# DogGone.net
KiCad netlist of a schematic drawn in EAGLE
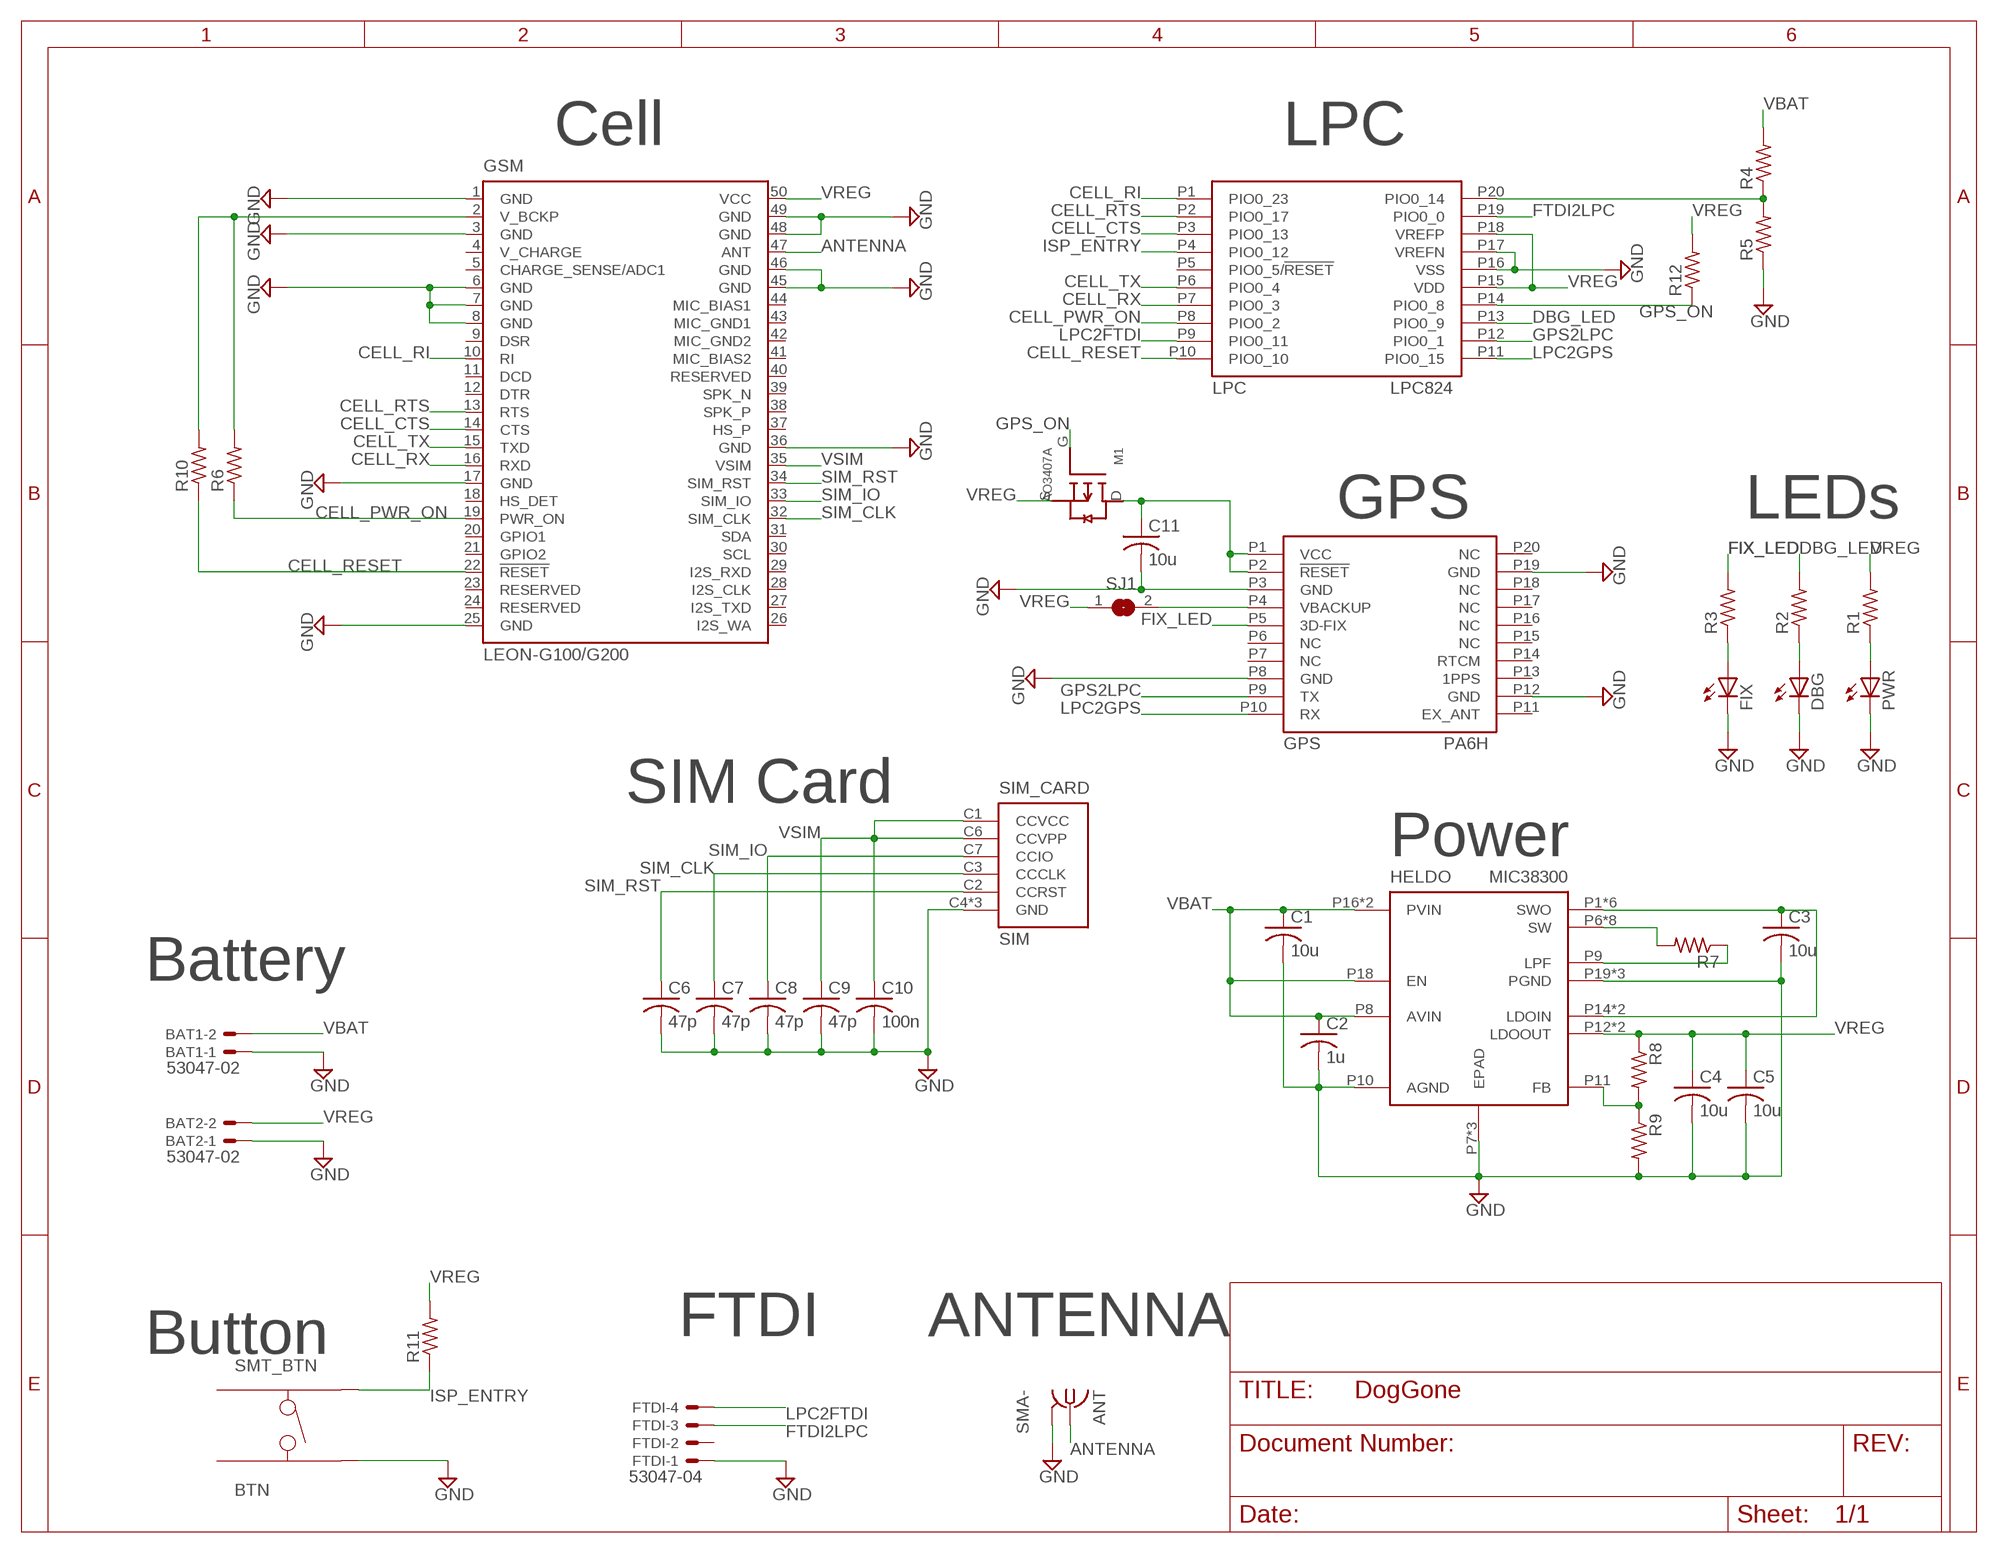
[diagram p0: schematic, sheet 1]

(export (version "E")
  (design (tool "Eeschema 10.0.6"))
  (components
    (comp (ref "ANT")
      (value "SMA-")
      (footprint "eagle-import:J502-ND-142-0701-801_806")
      (libsource (lib "eagle-import") (part "SMA-"))
    )
    (comp (ref "BAT1")
      (value "53047-02")
      (footprint "eagle-import:53047-02")
      (fields (field (name "MF") "MOLEX") (field (name "MPN") "53047-0210"))
      (libsource (lib "eagle-import") (part "53?-02047"))
    )
    (comp (ref "BAT2")
      (value "53047-02")
      (footprint "eagle-import:53047-02")
      (fields (field (name "MF") "MOLEX") (field (name "MPN") "53047-0210"))
      (libsource (lib "eagle-import") (part "53?-02047"))
    )
    (comp (ref "BTN")
      (value "SMT_BTN")
      (footprint "eagle-import:SMT_BUTTON")
      (libsource (lib "eagle-import") (part "SMT_BTN"))
    )
    (comp (ref "C1")
      (value "10u")
      (footprint "eagle-import:0603")
      (libsource (lib "eagle-import") (part "C0603"))
    )
    (comp (ref "C2")
      (value "1u")
      (footprint "eagle-import:0603")
      (libsource (lib "eagle-import") (part "C0603"))
    )
    (comp (ref "C3")
      (value "10u")
      (footprint "eagle-import:0603")
      (libsource (lib "eagle-import") (part "C0603"))
    )
    (comp (ref "C4")
      (value "10u")
      (footprint "eagle-import:0603")
      (libsource (lib "eagle-import") (part "C0603"))
    )
    (comp (ref "C5")
      (value "10u")
      (footprint "eagle-import:0603")
      (libsource (lib "eagle-import") (part "C0603"))
    )
    (comp (ref "C6")
      (value "47p")
      (footprint "eagle-import:0603")
      (libsource (lib "eagle-import") (part "C0603"))
    )
    (comp (ref "C7")
      (value "47p")
      (footprint "eagle-import:0603")
      (libsource (lib "eagle-import") (part "C0603"))
    )
    (comp (ref "C8")
      (value "47p")
      (footprint "eagle-import:0603")
      (libsource (lib "eagle-import") (part "C0603"))
    )
    (comp (ref "C9")
      (value "47p")
      (footprint "eagle-import:0603")
      (libsource (lib "eagle-import") (part "C0603"))
    )
    (comp (ref "C10")
      (value "100n")
      (footprint "eagle-import:0603")
      (libsource (lib "eagle-import") (part "C0603"))
    )
    (comp (ref "C11")
      (value "10u")
      (footprint "eagle-import:0603")
      (libsource (lib "eagle-import") (part "C0603"))
    )
    (comp (ref "DBG")
      (value "LEDCHIPLED_0603")
      (footprint "eagle-import:CHIPLED_0603")
      (libsource (lib "eagle-import") (part "LEDCHIPLED_0603"))
    )
    (comp (ref "FIX")
      (value "LEDCHIPLED_0603")
      (footprint "eagle-import:CHIPLED_0603")
      (libsource (lib "eagle-import") (part "LEDCHIPLED_0603"))
    )
    (comp (ref "FTDI")
      (value "53047-04")
      (footprint "eagle-import:53047-04")
      (fields (field (name "MF") "WALDOM/MOLEX") (field (name "MPN") "53047-0410"))
      (libsource (lib "eagle-import") (part "53?-04047"))
    )
    (comp (ref "GPS")
      (value "PA6H")
      (footprint "eagle-import:DFN20")
      (libsource (lib "eagle-import") (part "PA6H"))
    )
    (comp (ref "GSM")
      (value "LEON-G100/G200")
      (footprint "eagle-import:LEON-G100_G200")
      (libsource (lib "eagle-import") (part "LEON-G100/G200"))
    )
    (comp (ref "HELDO")
      (value "MIC38300")
      (footprint "eagle-import:MLF")
      (libsource (lib "eagle-import") (part "MIC38300_HELDO"))
    )
    (comp (ref "LPC")
      (value "LPC824")
      (footprint "eagle-import:TSSOP20")
      (libsource (lib "eagle-import") (part "LPC824M201JDH20"))
    )
    (comp (ref "M1")
      (value "AO3407A")
      (footprint "eagle-import:SOT23")
      (libsource (lib "eagle-import") (part "AO3407A"))
    )
    (comp (ref "PWR")
      (value "LEDCHIPLED_0603")
      (footprint "eagle-import:CHIPLED_0603")
      (libsource (lib "eagle-import") (part "LEDCHIPLED_0603"))
    )
    (comp (ref "R1")
      (value "R0603")
      (footprint "eagle-import:R0603")
      (libsource (lib "eagle-import") (part "R0603"))
    )
    (comp (ref "R2")
      (value "R0603")
      (footprint "eagle-import:R0603")
      (libsource (lib "eagle-import") (part "R0603"))
    )
    (comp (ref "R3")
      (value "R0603")
      (footprint "eagle-import:R0603")
      (libsource (lib "eagle-import") (part "R0603"))
    )
    (comp (ref "R4")
      (value "R0603")
      (footprint "eagle-import:R0603")
      (libsource (lib "eagle-import") (part "R0603"))
    )
    (comp (ref "R5")
      (value "R0603")
      (footprint "eagle-import:R0603")
      (libsource (lib "eagle-import") (part "R0603"))
    )
    (comp (ref "R6")
      (value "R0603")
      (footprint "eagle-import:R0603")
      (libsource (lib "eagle-import") (part "R0603"))
    )
    (comp (ref "R7")
      (value "R0603")
      (footprint "eagle-import:R0603")
      (libsource (lib "eagle-import") (part "R0603"))
    )
    (comp (ref "R8")
      (value "R0603")
      (footprint "eagle-import:R0603")
      (libsource (lib "eagle-import") (part "R0603"))
    )
    (comp (ref "R9")
      (value "R0603")
      (footprint "eagle-import:R0603")
      (libsource (lib "eagle-import") (part "R0603"))
    )
    (comp (ref "R10")
      (value "R0603")
      (footprint "eagle-import:R0603")
      (libsource (lib "eagle-import") (part "R0603"))
    )
    (comp (ref "R11")
      (value "R0603")
      (footprint "eagle-import:R0603")
      (libsource (lib "eagle-import") (part "R0603"))
    )
    (comp (ref "R12")
      (value "R0603")
      (footprint "eagle-import:R0603")
      (libsource (lib "eagle-import") (part "R0603"))
    )
    (comp (ref "SIM")
      (value "SIM_CARD")
      (footprint "eagle-import:SIM8050")
      (libsource (lib "eagle-import") (part "SIM_CARD"))
    )
    (comp (ref "SJ1") (value "SJ") (footprint "eagle-import:SJ") (libsource (lib "eagle-import") (part "SJ")))
  )
  (nets
    (net (code "1") (name "/ANTENNA") (class "Default")
      (node (ref "ANT") (pin "1") (pinfunction "1_1") (pintype "passive"))
      (node (ref "GSM") (pin "47") (pinfunction "ANT_47") (pintype "bidirectional"))
    )
    (net (code "2") (name "/CELL_CTS") (class "Default")
      (node (ref "GSM") (pin "14") (pinfunction "CTS_14") (pintype "input"))
      (node (ref "LPC") (pin "P3") (pinfunction "PIO0_13_P3") (pintype "bidirectional"))
    )
    (net (code "3") (name "/CELL_PWR_ON") (class "Default")
      (node (ref "GSM") (pin "19") (pinfunction "PWR_ON_19") (pintype "input"))
      (node (ref "LPC") (pin "P8") (pinfunction "PIO0_2_P8") (pintype "bidirectional"))
      (node (ref "R6") (pin "1") (pinfunction "1_1") (pintype "passive"))
    )
    (net (code "4") (name "/CELL_RESET") (class "Default")
      (node (ref "GSM") (pin "22") (pinfunction "~{RESET}_22") (pintype "input"))
      (node (ref "LPC") (pin "P10") (pinfunction "PIO0_10_P10") (pintype "bidirectional"))
      (node (ref "R10") (pin "1") (pinfunction "1_1") (pintype "passive"))
    )
    (net (code "5") (name "/CELL_RI") (class "Default")
      (node (ref "GSM") (pin "10") (pinfunction "RI_10") (pintype "input"))
      (node (ref "LPC") (pin "P1") (pinfunction "PIO0_23_P1") (pintype "bidirectional"))
    )
    (net (code "6") (name "/CELL_RTS") (class "Default")
      (node (ref "GSM") (pin "13") (pinfunction "RTS_13") (pintype "output"))
      (node (ref "LPC") (pin "P2") (pinfunction "PIO0_17_P2") (pintype "bidirectional"))
    )
    (net (code "7") (name "/CELL_RX") (class "Default")
      (node (ref "GSM") (pin "16") (pinfunction "RXD_16") (pintype "input"))
      (node (ref "LPC") (pin "P7") (pinfunction "PIO0_3_P7") (pintype "bidirectional"))
    )
    (net (code "8") (name "/CELL_TX") (class "Default")
      (node (ref "GSM") (pin "15") (pinfunction "TXD_15") (pintype "output"))
      (node (ref "LPC") (pin "P6") (pinfunction "PIO0_4_P6") (pintype "bidirectional"))
    )
    (net (code "9") (name "/DBG_LED") (class "Default")
      (node (ref "LPC") (pin "P13") (pinfunction "PIO0_9_P13") (pintype "bidirectional"))
      (node (ref "R2") (pin "2") (pinfunction "2_2") (pintype "passive"))
    )
    (net (code "10") (name "/FIX_LED") (class "Default")
      (node (ref "GPS") (pin "P5") (pinfunction "3D-FIX_P5") (pintype "bidirectional"))
      (node (ref "R3") (pin "2") (pinfunction "2_2") (pintype "passive"))
    )
    (net (code "11") (name "/FTDI2LPC") (class "Default")
      (node (ref "FTDI") (pin "3") (pinfunction "S_3") (pintype "passive"))
      (node (ref "LPC") (pin "P19") (pinfunction "PIO0_0_P19") (pintype "bidirectional"))
    )
    (net (code "12") (name "/GPS2LPC") (class "Default")
      (node (ref "GPS") (pin "P9") (pinfunction "TX_P9") (pintype "bidirectional"))
      (node (ref "LPC") (pin "P12") (pinfunction "PIO0_1_P12") (pintype "bidirectional"))
    )
    (net (code "13") (name "/GPS_ON") (class "Default")
      (node (ref "LPC") (pin "P14") (pinfunction "PIO0_8_P14") (pintype "bidirectional"))
      (node (ref "M1") (pin "G") (pinfunction "G_G") (pintype "bidirectional"))
      (node (ref "R12") (pin "1") (pinfunction "1_1") (pintype "passive"))
    )
    (net (code "14") (name "/ISP_ENTRY") (class "Default")
      (node (ref "BTN") (pin "P2") (pinfunction "P$2_P2") (pintype "bidirectional"))
      (node (ref "LPC") (pin "P4") (pinfunction "PIO0_12_P4") (pintype "bidirectional"))
      (node (ref "R11") (pin "1") (pinfunction "1_1") (pintype "passive"))
    )
    (net (code "15") (name "/LPC2FTDI") (class "Default")
      (node (ref "FTDI") (pin "4") (pinfunction "S_4") (pintype "passive"))
      (node (ref "LPC") (pin "P9") (pinfunction "PIO0_11_P9") (pintype "bidirectional"))
    )
    (net (code "16") (name "/LPC2GPS") (class "Default")
      (node (ref "GPS") (pin "P10") (pinfunction "RX_P10") (pintype "bidirectional"))
      (node (ref "LPC") (pin "P11") (pinfunction "PIO0_15_P11") (pintype "bidirectional"))
    )
    (net (code "17") (name "/SIM_CLK") (class "Default")
      (node (ref "C7") (pin "1") (pinfunction "1_1") (pintype "passive"))
      (node (ref "GSM") (pin "32") (pinfunction "SIM_CLK_32") (pintype "input"))
      (node (ref "SIM") (pin "C3") (pinfunction "CCCLK_C3") (pintype "bidirectional"))
    )
    (net (code "18") (name "/SIM_IO") (class "Default")
      (node (ref "C8") (pin "1") (pinfunction "1_1") (pintype "passive"))
      (node (ref "GSM") (pin "33") (pinfunction "SIM_IO_33") (pintype "input"))
      (node (ref "SIM") (pin "C7") (pinfunction "CCIO_C7") (pintype "bidirectional"))
    )
    (net (code "19") (name "/SIM_RST") (class "Default")
      (node (ref "C6") (pin "1") (pinfunction "1_1") (pintype "passive"))
      (node (ref "GSM") (pin "34") (pinfunction "SIM_RST_34") (pintype "input"))
      (node (ref "SIM") (pin "C2") (pinfunction "CCRST_C2") (pintype "bidirectional"))
    )
    (net (code "20") (name "/VBAT") (class "Default")
      (node (ref "BAT1") (pin "2") (pinfunction "S_2") (pintype "passive"))
      (node (ref "C1") (pin "1") (pinfunction "1_1") (pintype "passive"))
      (node (ref "C2") (pin "1") (pinfunction "1_1") (pintype "passive"))
      (node (ref "HELDO") (pin "P16") (pinfunction "PVIN_P16") (pintype "power_in"))
      (node (ref "HELDO") (pin "P17") (pinfunction "PVIN_P17") (pintype "power_in"))
      (node (ref "HELDO") (pin "P18") (pinfunction "EN_P18") (pintype "bidirectional"))
      (node (ref "HELDO") (pin "P8") (pinfunction "AVIN_P8") (pintype "power_in"))
      (node (ref "R4") (pin "2") (pinfunction "2_2") (pintype "passive"))
    )
    (net (code "21") (name "/VREG") (class "Default")
      (node (ref "BAT2") (pin "2") (pinfunction "S_2") (pintype "passive"))
      (node (ref "C4") (pin "1") (pinfunction "1_1") (pintype "passive"))
      (node (ref "C5") (pin "1") (pinfunction "1_1") (pintype "passive"))
      (node (ref "GSM") (pin "50") (pinfunction "VCC_50") (pintype "power_in"))
      (node (ref "HELDO") (pin "P12") (pinfunction "LDOOUT_P12") (pintype "power_in"))
      (node (ref "HELDO") (pin "P13") (pinfunction "LDOOUT_P13") (pintype "power_in"))
      (node (ref "LPC") (pin "P15") (pinfunction "VDD_P15") (pintype "power_in"))
      (node (ref "LPC") (pin "P18") (pinfunction "VREFP_P18") (pintype "bidirectional"))
      (node (ref "M1") (pin "S") (pinfunction "S_S") (pintype "bidirectional"))
      (node (ref "R1") (pin "2") (pinfunction "2_2") (pintype "passive"))
      (node (ref "R11") (pin "2") (pinfunction "2_2") (pintype "passive"))
      (node (ref "R12") (pin "2") (pinfunction "2_2") (pintype "passive"))
      (node (ref "R8") (pin "1") (pinfunction "1_1") (pintype "passive"))
      (node (ref "SJ1") (pin "1") (pinfunction "1_1") (pintype "passive"))
    )
    (net (code "22") (name "/VSIM") (class "Default")
      (node (ref "C10") (pin "1") (pinfunction "1_1") (pintype "passive"))
      (node (ref "C9") (pin "1") (pinfunction "1_1") (pintype "passive"))
      (node (ref "GSM") (pin "35") (pinfunction "VSIM_35") (pintype "input"))
      (node (ref "SIM") (pin "C1") (pinfunction "CCVCC_C1") (pintype "power_in"))
      (node (ref "SIM") (pin "C6") (pinfunction "CCVPP_C6") (pintype "power_in"))
    )
    (net (code "23") (name "GND") (class "Default")
      (node (ref "ANT") (pin "G@1") (pinfunction "GND_G@1") (pintype "passive"))
      (node (ref "ANT") (pin "G@2") (pinfunction "GND_G@2") (pintype "passive"))
      (node (ref "ANT") (pin "G@3") (pinfunction "GND_G@3") (pintype "passive"))
      (node (ref "ANT") (pin "G@4") (pinfunction "GND_G@4") (pintype "passive"))
      (node (ref "BAT1") (pin "1") (pinfunction "S_1") (pintype "passive"))
      (node (ref "BAT2") (pin "1") (pinfunction "S_1") (pintype "passive"))
      (node (ref "BTN") (pin "P4") (pinfunction "P$4_P4") (pintype "bidirectional"))
      (node (ref "C1") (pin "2") (pinfunction "2_2") (pintype "passive"))
      (node (ref "C10") (pin "2") (pinfunction "2_2") (pintype "passive"))
      (node (ref "C11") (pin "2") (pinfunction "2_2") (pintype "passive"))
      (node (ref "C2") (pin "2") (pinfunction "2_2") (pintype "passive"))
      (node (ref "C3") (pin "2") (pinfunction "2_2") (pintype "passive"))
      (node (ref "C4") (pin "2") (pinfunction "2_2") (pintype "passive"))
      (node (ref "C5") (pin "2") (pinfunction "2_2") (pintype "passive"))
      (node (ref "C6") (pin "2") (pinfunction "2_2") (pintype "passive"))
      (node (ref "C7") (pin "2") (pinfunction "2_2") (pintype "passive"))
      (node (ref "C8") (pin "2") (pinfunction "2_2") (pintype "passive"))
      (node (ref "C9") (pin "2") (pinfunction "2_2") (pintype "passive"))
      (node (ref "DBG") (pin "C") (pinfunction "C_C") (pintype "passive"))
      (node (ref "FIX") (pin "C") (pinfunction "C_C") (pintype "passive"))
      (node (ref "FTDI") (pin "1") (pinfunction "S_1") (pintype "passive"))
      (node (ref "GPS") (pin "P12") (pinfunction "GND_P12") (pintype "power_in"))
      (node (ref "GPS") (pin "P19") (pinfunction "GND_P19") (pintype "power_in"))
      (node (ref "GPS") (pin "P3") (pinfunction "GND_P3") (pintype "power_in"))
      (node (ref "GPS") (pin "P8") (pinfunction "GND_P8") (pintype "power_in"))
      (node (ref "GSM") (pin "1") (pinfunction "GND_1") (pintype "power_in"))
      (node (ref "GSM") (pin "17") (pinfunction "GND_17") (pintype "power_in"))
      (node (ref "GSM") (pin "25") (pinfunction "GND_25") (pintype "power_in"))
      (node (ref "GSM") (pin "3") (pinfunction "GND_3") (pintype "power_in"))
      (node (ref "GSM") (pin "36") (pinfunction "GND_36") (pintype "power_in"))
      (node (ref "GSM") (pin "45") (pinfunction "GND_45") (pintype "power_in"))
      (node (ref "GSM") (pin "46") (pinfunction "GND_46") (pintype "power_in"))
      (node (ref "GSM") (pin "48") (pinfunction "GND_48") (pintype "power_in"))
      (node (ref "GSM") (pin "49") (pinfunction "GND_49") (pintype "power_in"))
      (node (ref "GSM") (pin "6") (pinfunction "GND_6") (pintype "power_in"))
      (node (ref "GSM") (pin "7") (pinfunction "GND_7") (pintype "power_in"))
      (node (ref "GSM") (pin "8") (pinfunction "GND_8") (pintype "power_in"))
      (node (ref "HELDO") (pin "P10") (pinfunction "AGND_P10") (pintype "bidirectional"))
      (node (ref "HELDO") (pin "P19") (pinfunction "PGND_P19") (pintype "power_in"))
      (node (ref "HELDO") (pin "P20") (pinfunction "PGND_P20") (pintype "power_in"))
      (node (ref "HELDO") (pin "P21") (pinfunction "PGND_P21") (pintype "power_in"))
      (node (ref "HELDO") (pin "P22") (pinfunction "EPAD_P22") (pintype "power_in"))
      (node (ref "HELDO") (pin "P7") (pinfunction "EPAD_P7") (pintype "power_in"))
      (node (ref "HELDO") (pin "P8-21") (pinfunction "EPAD_P8-21") (pintype "power_in"))
      (node (ref "LPC") (pin "P16") (pinfunction "VSS_P16") (pintype "power_in"))
      (node (ref "LPC") (pin "P17") (pinfunction "VREFN_P17") (pintype "bidirectional"))
      (node (ref "PWR") (pin "C") (pinfunction "C_C") (pintype "passive"))
      (node (ref "R5") (pin "1") (pinfunction "1_1") (pintype "passive"))
      (node (ref "R9") (pin "2") (pinfunction "2_2") (pintype "passive"))
      (node (ref "SIM") (pin "C4") (pinfunction "GND_C4") (pintype "power_in"))
      (node (ref "SIM") (pin "C5") (pinfunction "GND_C5") (pintype "power_in"))
      (node (ref "SIM") (pin "C8") (pinfunction "GND_C8") (pintype "power_in"))
    )
    (net (code "24") (name "Net-(C3-Pad1)") (class "Default")
      (node (ref "C3") (pin "1") (pinfunction "1_1") (pintype "passive"))
      (node (ref "HELDO") (pin "P1") (pinfunction "SWO_P1") (pintype "passive"))
      (node (ref "HELDO") (pin "P1-5") (pinfunction "SWO_P1-5") (pintype "passive"))
      (node (ref "HELDO") (pin "P14") (pinfunction "LDOIN_P14") (pintype "power_in"))
      (node (ref "HELDO") (pin "P15") (pinfunction "LDOIN_P15") (pintype "power_in"))
      (node (ref "HELDO") (pin "P2") (pinfunction "SWO_P2") (pintype "passive"))
      (node (ref "HELDO") (pin "P3") (pinfunction "SWO_P3") (pintype "passive"))
      (node (ref "HELDO") (pin "P4") (pinfunction "SWO_P4") (pintype "passive"))
      (node (ref "HELDO") (pin "P5") (pinfunction "SWO_P5") (pintype "passive"))
    )
    (net (code "25") (name "Net-(DBG-PadA)") (class "Default")
      (node (ref "DBG") (pin "A") (pinfunction "A_A") (pintype "passive"))
      (node (ref "R2") (pin "1") (pinfunction "1_1") (pintype "passive"))
    )
    (net (code "26") (name "Net-(FIX-PadA)") (class "Default")
      (node (ref "FIX") (pin "A") (pinfunction "A_A") (pintype "passive"))
      (node (ref "R3") (pin "1") (pinfunction "1_1") (pintype "passive"))
    )
    (net (code "27") (name "Net-(GPS-VBACKUP)") (class "Default")
      (node (ref "GPS") (pin "P4") (pinfunction "VBACKUP_P4") (pintype "power_in"))
      (node (ref "SJ1") (pin "2") (pinfunction "2_2") (pintype "passive"))
    )
    (net (code "28") (name "Net-(GPS-VCC)") (class "Default")
      (node (ref "C11") (pin "1") (pinfunction "1_1") (pintype "passive"))
      (node (ref "GPS") (pin "P1") (pinfunction "VCC_P1") (pintype "power_in"))
      (node (ref "GPS") (pin "P2") (pinfunction "~{RESET}_P2") (pintype "bidirectional"))
      (node (ref "M1") (pin "D") (pinfunction "D_D") (pintype "bidirectional"))
    )
    (net (code "29") (name "Net-(GSM-V_BCKP)") (class "Default")
      (node (ref "GSM") (pin "2") (pinfunction "V_BCKP_2") (pintype "input"))
      (node (ref "R10") (pin "2") (pinfunction "2_2") (pintype "passive"))
      (node (ref "R6") (pin "2") (pinfunction "2_2") (pintype "passive"))
    )
    (net (code "30") (name "Net-(HELDO-FB)") (class "Default")
      (node (ref "HELDO") (pin "P11") (pinfunction "FB_P11") (pintype "bidirectional"))
      (node (ref "R8") (pin "2") (pinfunction "2_2") (pintype "passive"))
      (node (ref "R9") (pin "1") (pinfunction "1_1") (pintype "passive"))
    )
    (net (code "31") (name "Net-(HELDO-LPF)") (class "Default")
      (node (ref "HELDO") (pin "P9") (pinfunction "LPF_P9") (pintype "bidirectional"))
      (node (ref "R7") (pin "1") (pinfunction "1_1") (pintype "passive"))
    )
    (net (code "32") (name "Net-(HELDO-SW-PadP23)") (class "Default")
      (node (ref "HELDO") (pin "P23") (pinfunction "SW_P23") (pintype "bidirectional"))
      (node (ref "HELDO") (pin "P23-28") (pinfunction "SW_P23-28") (pintype "bidirectional"))
      (node (ref "HELDO") (pin "P24") (pinfunction "SW_P24") (pintype "bidirectional"))
      (node (ref "HELDO") (pin "P25") (pinfunction "SW_P25") (pintype "bidirectional"))
      (node (ref "HELDO") (pin "P26") (pinfunction "SW_P26") (pintype "bidirectional"))
      (node (ref "HELDO") (pin "P27") (pinfunction "SW_P27") (pintype "bidirectional"))
      (node (ref "HELDO") (pin "P28") (pinfunction "SW_P28") (pintype "bidirectional"))
      (node (ref "HELDO") (pin "P6") (pinfunction "SW_P6") (pintype "bidirectional"))
      (node (ref "R7") (pin "2") (pinfunction "2_2") (pintype "passive"))
    )
    (net (code "33") (name "Net-(LPC-PIO0_14)") (class "Default")
      (node (ref "LPC") (pin "P20") (pinfunction "PIO0_14_P20") (pintype "bidirectional"))
      (node (ref "R4") (pin "1") (pinfunction "1_1") (pintype "passive"))
      (node (ref "R5") (pin "2") (pinfunction "2_2") (pintype "passive"))
    )
    (net (code "34") (name "Net-(PWR-PadA)") (class "Default")
      (node (ref "PWR") (pin "A") (pinfunction "A_A") (pintype "passive"))
      (node (ref "R1") (pin "1") (pinfunction "1_1") (pintype "passive"))
    )
    (net (code "35") (name "unconnected-(BTN-P$1-PadP1)") (class "Default")
      (node (ref "BTN") (pin "P1") (pinfunction "P$1_P1") (pintype "bidirectional"))
    )
    (net (code "36") (name "unconnected-(BTN-P$3-PadP3)") (class "Default")
      (node (ref "BTN") (pin "P3") (pinfunction "P$3_P3") (pintype "bidirectional"))
    )
    (net (code "37") (name "unconnected-(FTDIB-S-Pad2)") (class "Default")
      (node (ref "FTDI") (pin "2") (pinfunction "S_2") (pintype "passive"))
    )
    (net (code "38") (name "unconnected-(GPS-1PPS-PadP13)") (class "Default")
      (node (ref "GPS") (pin "P13") (pinfunction "1PPS_P13") (pintype "bidirectional"))
    )
    (net (code "39") (name "unconnected-(GPS-EX_ANT-PadP11)") (class "Default")
      (node (ref "GPS") (pin "P11") (pinfunction "EX_ANT_P11") (pintype "passive"))
    )
    (net (code "40") (name "unconnected-(GPS-NC-PadP6)") (class "Default")
      (node (ref "GPS") (pin "P6") (pinfunction "NC_P6") (pintype "no_connect"))
    )
    (net (code "41") (name "unconnected-(GPS-NC-PadP7)") (class "Default")
      (node (ref "GPS") (pin "P7") (pinfunction "NC_P7") (pintype "no_connect"))
    )
    (net (code "42") (name "unconnected-(GPS-NC-PadP15)") (class "Default")
      (node (ref "GPS") (pin "P15") (pinfunction "NC_P15") (pintype "no_connect"))
    )
    (net (code "43") (name "unconnected-(GPS-NC-PadP16)") (class "Default")
      (node (ref "GPS") (pin "P16") (pinfunction "NC_P16") (pintype "no_connect"))
    )
    (net (code "44") (name "unconnected-(GPS-NC-PadP17)") (class "Default")
      (node (ref "GPS") (pin "P17") (pinfunction "NC_P17") (pintype "no_connect"))
    )
    (net (code "45") (name "unconnected-(GPS-NC-PadP18)") (class "Default")
      (node (ref "GPS") (pin "P18") (pinfunction "NC_P18") (pintype "no_connect"))
    )
    (net (code "46") (name "unconnected-(GPS-NC-PadP20)") (class "Default")
      (node (ref "GPS") (pin "P20") (pinfunction "NC_P20") (pintype "no_connect"))
    )
    (net (code "47") (name "unconnected-(GPS-RTCM-PadP14)") (class "Default")
      (node (ref "GPS") (pin "P14") (pinfunction "RTCM_P14") (pintype "bidirectional"))
    )
    (net (code "48") (name "unconnected-(GSM-CHARGE_SENSE{slash}ADC1-Pad5)") (class "Default")
      (node (ref "GSM") (pin "5") (pinfunction "CHARGE_SENSE/ADC1_5") (pintype "input"))
    )
    (net (code "49") (name "unconnected-(GSM-DCD-Pad11)") (class "Default")
      (node (ref "GSM") (pin "11") (pinfunction "DCD_11") (pintype "input"))
    )
    (net (code "50") (name "unconnected-(GSM-DSR-Pad9)") (class "Default")
      (node (ref "GSM") (pin "9") (pinfunction "DSR_9") (pintype "input"))
    )
    (net (code "51") (name "unconnected-(GSM-DTR-Pad12)") (class "Default")
      (node (ref "GSM") (pin "12") (pinfunction "DTR_12") (pintype "input"))
    )
    (net (code "52") (name "unconnected-(GSM-GPIO1-Pad20)") (class "Default")
      (node (ref "GSM") (pin "20") (pinfunction "GPIO1_20") (pintype "input"))
    )
    (net (code "53") (name "unconnected-(GSM-GPIO2-Pad21)") (class "Default")
      (node (ref "GSM") (pin "21") (pinfunction "GPIO2_21") (pintype "input"))
    )
    (net (code "54") (name "unconnected-(GSM-HS_DET-Pad18)") (class "Default")
      (node (ref "GSM") (pin "18") (pinfunction "HS_DET_18") (pintype "input"))
    )
    (net (code "55") (name "unconnected-(GSM-HS_P-Pad37)") (class "Default")
      (node (ref "GSM") (pin "37") (pinfunction "HS_P_37") (pintype "output"))
    )
    (net (code "56") (name "unconnected-(GSM-I2S_CLK-Pad28)") (class "Default")
      (node (ref "GSM") (pin "28") (pinfunction "I2S_CLK_28") (pintype "output"))
    )
    (net (code "57") (name "unconnected-(GSM-I2S_RXD-Pad29)") (class "Default")
      (node (ref "GSM") (pin "29") (pinfunction "I2S_RXD_29") (pintype "output"))
    )
    (net (code "58") (name "unconnected-(GSM-I2S_TXD-Pad27)") (class "Default")
      (node (ref "GSM") (pin "27") (pinfunction "I2S_TXD_27") (pintype "output"))
    )
    (net (code "59") (name "unconnected-(GSM-I2S_WA-Pad26)") (class "Default")
      (node (ref "GSM") (pin "26") (pinfunction "I2S_WA_26") (pintype "output"))
    )
    (net (code "60") (name "unconnected-(GSM-MIC_BIAS1-Pad44)") (class "Default")
      (node (ref "GSM") (pin "44") (pinfunction "MIC_BIAS1_44") (pintype "input"))
    )
    (net (code "61") (name "unconnected-(GSM-MIC_BIAS2-Pad41)") (class "Default")
      (node (ref "GSM") (pin "41") (pinfunction "MIC_BIAS2_41") (pintype "input"))
    )
    (net (code "62") (name "unconnected-(GSM-MIC_GND1-Pad43)") (class "Default")
      (node (ref "GSM") (pin "43") (pinfunction "MIC_GND1_43") (pintype "passive"))
    )
    (net (code "63") (name "unconnected-(GSM-MIC_GND2-Pad42)") (class "Default")
      (node (ref "GSM") (pin "42") (pinfunction "MIC_GND2_42") (pintype "passive"))
    )
    (net (code "64") (name "unconnected-(GSM-RESERVED-Pad23)") (class "Default")
      (node (ref "GSM") (pin "23") (pinfunction "RESERVED_23") (pintype "passive"))
    )
    (net (code "65") (name "unconnected-(GSM-RESERVED-Pad24)") (class "Default")
      (node (ref "GSM") (pin "24") (pinfunction "RESERVED_24") (pintype "passive"))
    )
    (net (code "66") (name "unconnected-(GSM-RESERVED-Pad40)") (class "Default")
      (node (ref "GSM") (pin "40") (pinfunction "RESERVED_40") (pintype "passive"))
    )
    (net (code "67") (name "unconnected-(GSM-SCL-Pad30)") (class "Default")
      (node (ref "GSM") (pin "30") (pinfunction "SCL_30") (pintype "input"))
    )
    (net (code "68") (name "unconnected-(GSM-SDA-Pad31)") (class "Default")
      (node (ref "GSM") (pin "31") (pinfunction "SDA_31") (pintype "input"))
    )
    (net (code "69") (name "unconnected-(GSM-SPK_N-Pad39)") (class "Default")
      (node (ref "GSM") (pin "39") (pinfunction "SPK_N_39") (pintype "output"))
    )
    (net (code "70") (name "unconnected-(GSM-SPK_P-Pad38)") (class "Default")
      (node (ref "GSM") (pin "38") (pinfunction "SPK_P_38") (pintype "output"))
    )
    (net (code "71") (name "unconnected-(GSM-V_CHARGE-Pad4)") (class "Default")
      (node (ref "GSM") (pin "4") (pinfunction "V_CHARGE_4") (pintype "input"))
    )
    (net (code "72") (name "unconnected-(LPC-PIO0_5{slash}~{RESET}-PadP5)") (class "Default")
      (node (ref "LPC") (pin "P5") (pinfunction "PIO0_5/~{RESET}_P5") (pintype "bidirectional"))
    )
  )
)
